# Power_Supply.net
KiCad netlist of a schematic drawn in Altium Designer
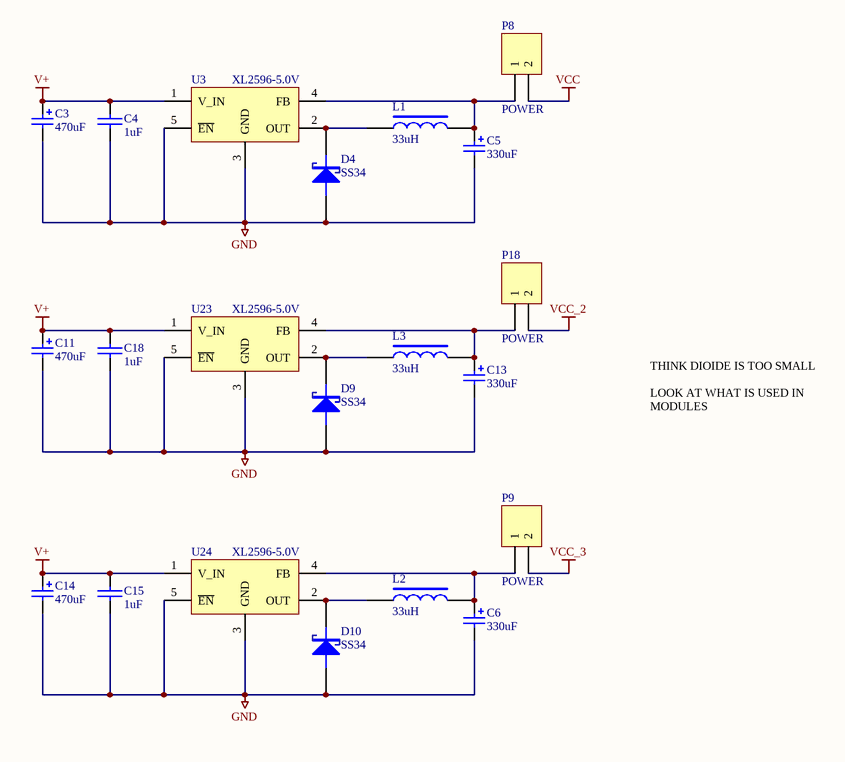
[diagram p0: Power Supply.SchDoc]

(export (version "E")
  (design (tool "Eeschema 10.0.6"))
  (components
    (comp (ref "C3")
      (value "470uF")
      (footprint "CAP 10Dx16Hx5P")
      (description "Polarized Capacitor (Radial)")
      (fields (field (name "LCSC PART NUMBER") "C698136"))
      (libsource (lib "Low Cost Labs") (part "Aluminum 10Dx16Hx5P"))
    )
    (comp (ref "C4")
      (value "1uF")
      (footprint "CAP 1206")
      (description "CAPACITOR SMD 0603")
      (fields (field (name "LCSC PART NUMBER") "C91151"))
      (libsource (lib "Mi-Call Schematic") (part "CAP"))
    )
    (comp (ref "C5")
      (value "330uF")
      (footprint "CAP 10Dx16Hx5P")
      (description "Polarized Capacitor (Radial)")
      (fields (field (name "LCSC PART NUMBER") "C698136"))
      (libsource (lib "Low Cost Labs") (part "Aluminum 10Dx16Hx5P"))
    )
    (comp (ref "C6")
      (value "330uF")
      (footprint "CAP 10Dx16Hx5P")
      (description "Polarized Capacitor (Radial)")
      (fields (field (name "LCSC PART NUMBER") "C698136"))
      (libsource (lib "Low Cost Labs") (part "Aluminum 10Dx16Hx5P"))
    )
    (comp (ref "C11")
      (value "470uF")
      (footprint "CAP 10Dx16Hx5P")
      (description "Polarized Capacitor (Radial)")
      (fields (field (name "LCSC PART NUMBER") "C698136"))
      (libsource (lib "Low Cost Labs") (part "Aluminum 10Dx16Hx5P"))
    )
    (comp (ref "C13")
      (value "330uF")
      (footprint "CAP 10Dx16Hx5P")
      (description "Polarized Capacitor (Radial)")
      (fields (field (name "LCSC PART NUMBER") "C698136"))
      (libsource (lib "Low Cost Labs") (part "Aluminum 10Dx16Hx5P"))
    )
    (comp (ref "C14")
      (value "470uF")
      (footprint "CAP 10Dx16Hx5P")
      (description "Polarized Capacitor (Radial)")
      (fields (field (name "LCSC PART NUMBER") "C698136"))
      (libsource (lib "Low Cost Labs") (part "Aluminum 10Dx16Hx5P"))
    )
    (comp (ref "C15")
      (value "1uF")
      (footprint "CAP 1206")
      (description "CAPACITOR SMD 0603")
      (fields (field (name "LCSC PART NUMBER") "C91151"))
      (libsource (lib "Mi-Call Schematic") (part "CAP"))
    )
    (comp (ref "C18")
      (value "1uF")
      (footprint "CAP 1206")
      (description "CAPACITOR SMD 0603")
      (fields (field (name "LCSC PART NUMBER") "C91151"))
      (libsource (lib "Mi-Call Schematic") (part "CAP"))
    )
    (comp (ref "D4")
      (value "SS34")
      (footprint "DO-215AD (SOD123)")
      (description "DIODE, POWER")
      (fields (field (name "LCSC PART NUMBER") "C466502"))
      (libsource (lib "Low Cost Labs") (part "DIODE"))
    )
    (comp (ref "D9")
      (value "SS34")
      (footprint "DO-215AD (SOD123)")
      (description "DIODE, POWER")
      (fields (field (name "LCSC PART NUMBER") "C466502"))
      (libsource (lib "Low Cost Labs") (part "DIODE"))
    )
    (comp (ref "D10")
      (value "SS34")
      (footprint "DO-215AD (SOD123)")
      (description "DIODE, POWER")
      (fields (field (name "LCSC PART NUMBER") "C466502"))
      (libsource (lib "Low Cost Labs") (part "DIODE"))
    )
    (comp (ref "L1")
      (value "33uH")
      (footprint "12.3x12.3x6")
      (description "INDUCTOR SMD 1210")
      (fields (field (name "LCSC PART NUMBER") "C439422"))
      (libsource (lib "Low Cost Labs") (part "INDUCTOR SMD 1210 100uH"))
    )
    (comp (ref "L2")
      (value "33uH")
      (footprint "12.3x12.3x6")
      (description "INDUCTOR SMD 1210")
      (fields (field (name "LCSC PART NUMBER") "C439422"))
      (libsource (lib "Low Cost Labs") (part "INDUCTOR SMD 1210 100uH"))
    )
    (comp (ref "L3")
      (value "33uH")
      (footprint "12.3x12.3x6")
      (description "INDUCTOR SMD 1210")
      (fields (field (name "LCSC PART NUMBER") "C439422"))
      (libsource (lib "Low Cost Labs") (part "INDUCTOR SMD 1210 100uH"))
    )
    (comp (ref "P8")
      (value "POWER")
      (footprint "HEADER 1x2")
      (description "Header, 2-Pin")
      (fields (field (name "PUBLISHER") "Altium Limited"))
      (libsource (lib "XC Tail Light Driver") (part "Header 2"))
    )
    (comp (ref "P9")
      (value "POWER")
      (footprint "HEADER 1x2")
      (description "Header, 2-Pin")
      (fields (field (name "PUBLISHER") "Altium Limited"))
      (libsource (lib "XC Tail Light Driver") (part "Header 2"))
    )
    (comp (ref "P18")
      (value "POWER")
      (footprint "HEADER 1x2")
      (description "Header, 2-Pin")
      (fields (field (name "PUBLISHER") "Altium Limited"))
      (libsource (lib "XC Tail Light Driver") (part "Header 2"))
    )
    (comp (ref "U3")
      (value "XL2596-5.0V")
      (footprint "TO263-5")
      (description "XL2596-5.0")
      (fields (field (name "LCSC PART NUMBER") "C74190"))
      (libsource (lib "XC Tail Light Driver") (part "XL2596 -5.0 REGLATOR"))
    )
    (comp (ref "U23")
      (value "XL2596-5.0V")
      (footprint "TO263-5")
      (description "XL2596-5.0")
      (fields (field (name "LCSC PART NUMBER") "C74190"))
      (libsource (lib "XC Tail Light Driver") (part "XL2596 -5.0 REGLATOR"))
    )
    (comp (ref "U24")
      (value "XL2596-5.0V")
      (footprint "TO263-5")
      (description "XL2596-5.0")
      (fields (field (name "LCSC PART NUMBER") "C74190"))
      (libsource (lib "XC Tail Light Driver") (part "XL2596 -5.0 REGLATOR"))
    )
  )
  (nets
    (net (code "1") (name "GND") (class "Default")
      (node (ref "C11") (pin "2") (pinfunction "2_2") (pintype "passive"))
      (node (ref "C13") (pin "2") (pinfunction "2_2") (pintype "passive"))
      (node (ref "C14") (pin "2") (pinfunction "2_2") (pintype "passive"))
      (node (ref "C15") (pin "2") (pinfunction "2_2") (pintype "passive"))
      (node (ref "C18") (pin "2") (pinfunction "2_2") (pintype "passive"))
      (node (ref "C3") (pin "2") (pinfunction "2_2") (pintype "passive"))
      (node (ref "C4") (pin "2") (pinfunction "2_2") (pintype "passive"))
      (node (ref "C5") (pin "2") (pinfunction "2_2") (pintype "passive"))
      (node (ref "C6") (pin "2") (pinfunction "2_2") (pintype "passive"))
      (node (ref "D10") (pin "1") (pinfunction "A_1") (pintype "passive"))
      (node (ref "D4") (pin "1") (pinfunction "A_1") (pintype "passive"))
      (node (ref "D9") (pin "1") (pinfunction "A_1") (pintype "passive"))
      (node (ref "U23") (pin "3") (pinfunction "GND_3") (pintype "power_in"))
      (node (ref "U23") (pin "5") (pinfunction "~{EN}_5") (pintype "power_in"))
      (node (ref "U24") (pin "3") (pinfunction "GND_3") (pintype "power_in"))
      (node (ref "U24") (pin "5") (pinfunction "~{EN}_5") (pintype "power_in"))
      (node (ref "U3") (pin "3") (pinfunction "GND_3") (pintype "power_in"))
      (node (ref "U3") (pin "5") (pinfunction "~{EN}_5") (pintype "power_in"))
    )
    (net (code "2") (name "Net-(D4-K)") (class "Default")
      (node (ref "D4") (pin "2") (pinfunction "K_2") (pintype "passive"))
      (node (ref "L1") (pin "1") (pinfunction "1_1") (pintype "passive"))
      (node (ref "U3") (pin "2") (pinfunction "OUT_2") (pintype "power_in"))
    )
    (net (code "3") (name "Net-(D9-K)") (class "Default")
      (node (ref "D9") (pin "2") (pinfunction "K_2") (pintype "passive"))
      (node (ref "L3") (pin "1") (pinfunction "1_1") (pintype "passive"))
      (node (ref "U23") (pin "2") (pinfunction "OUT_2") (pintype "power_in"))
    )
    (net (code "4") (name "Net-(D10-K)") (class "Default")
      (node (ref "D10") (pin "2") (pinfunction "K_2") (pintype "passive"))
      (node (ref "L2") (pin "1") (pinfunction "1_1") (pintype "passive"))
      (node (ref "U24") (pin "2") (pinfunction "OUT_2") (pintype "power_in"))
    )
    (net (code "5") (name "Net-(U3-FB)") (class "Default")
      (node (ref "C5") (pin "1") (pinfunction "1_1") (pintype "passive"))
      (node (ref "L1") (pin "2") (pinfunction "2_2") (pintype "passive"))
      (node (ref "P8") (pin "1") (pinfunction "1_1") (pintype "passive"))
      (node (ref "U3") (pin "4") (pinfunction "FB_4") (pintype "power_in"))
    )
    (net (code "6") (name "Net-(U23-FB)") (class "Default")
      (node (ref "C13") (pin "1") (pinfunction "1_1") (pintype "passive"))
      (node (ref "L3") (pin "2") (pinfunction "2_2") (pintype "passive"))
      (node (ref "P18") (pin "1") (pinfunction "1_1") (pintype "passive"))
      (node (ref "U23") (pin "4") (pinfunction "FB_4") (pintype "power_in"))
    )
    (net (code "7") (name "Net-(U24-FB)") (class "Default")
      (node (ref "C6") (pin "1") (pinfunction "1_1") (pintype "passive"))
      (node (ref "L2") (pin "2") (pinfunction "2_2") (pintype "passive"))
      (node (ref "P9") (pin "1") (pinfunction "1_1") (pintype "passive"))
      (node (ref "U24") (pin "4") (pinfunction "FB_4") (pintype "power_in"))
    )
    (net (code "8") (name "V+") (class "Default")
      (node (ref "C11") (pin "1") (pinfunction "1_1") (pintype "passive"))
      (node (ref "C14") (pin "1") (pinfunction "1_1") (pintype "passive"))
      (node (ref "C15") (pin "1") (pinfunction "1_1") (pintype "passive"))
      (node (ref "C18") (pin "1") (pinfunction "1_1") (pintype "passive"))
      (node (ref "C3") (pin "1") (pinfunction "1_1") (pintype "passive"))
      (node (ref "C4") (pin "1") (pinfunction "1_1") (pintype "passive"))
      (node (ref "U23") (pin "1") (pinfunction "V_IN_1") (pintype "power_in"))
      (node (ref "U24") (pin "1") (pinfunction "V_IN_1") (pintype "power_in"))
      (node (ref "U3") (pin "1") (pinfunction "V_IN_1") (pintype "power_in"))
    )
    (net (code "9") (name "VCC") (class "Default")
      (node (ref "P8") (pin "2") (pinfunction "2_2") (pintype "passive"))
    )
    (net (code "10") (name "VCC_2") (class "Default")
      (node (ref "P18") (pin "2") (pinfunction "2_2") (pintype "passive"))
    )
    (net (code "11") (name "VCC_3") (class "Default")
      (node (ref "P9") (pin "2") (pinfunction "2_2") (pintype "passive"))
    )
  )
)
